# DcDc5V.net
KiCad netlist of a schematic drawn in Altium Designer
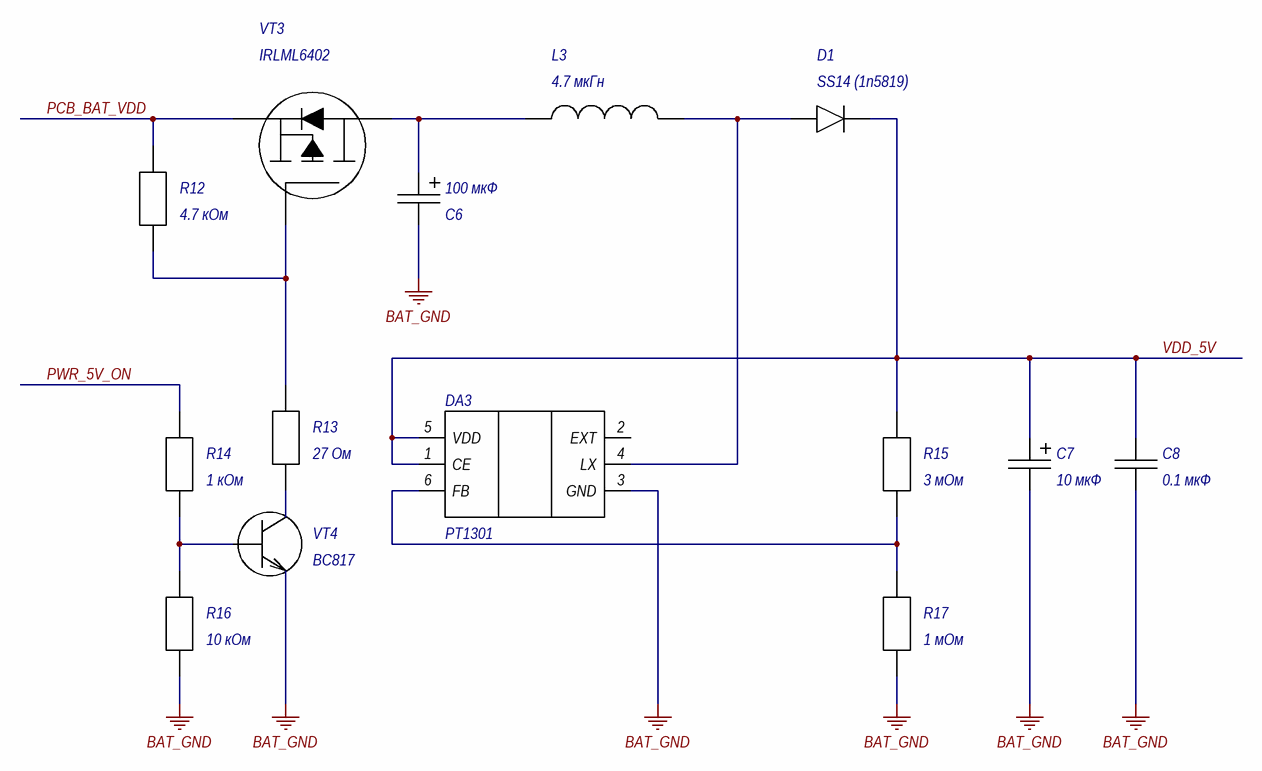
[diagram p0: DcDc5V.SchDoc]

(export (version "E")
  (design (tool "Eeschema 10.0.6"))
  (components
    (comp (ref "C6")
      (value "100 мкФ")
      (footprint "C TAN_C")
      (description "SMD Tantalium Capacitor C")
      (libsource (lib "my_lib") (part "CAP TAN_C"))
    )
    (comp (ref "C7")
      (value "10 мкФ")
      (footprint "C TAN_A")
      (description "SMD Tantalium Capacitor A")
      (libsource (lib "my_lib") (part "CAP TAN_A"))
    )
    (comp (ref "C8")
      (value "0.1 мкФ")
      (footprint "C 0805")
      (description "SMD Capacitor 0805")
      (fields
        (field (name "TOLERANCE") "/Укажите допуск в процентах/")
        (field (name "MANUFACTURER") "/Укажите компанию-производителя/")
      )
      (libsource (lib "my_lib") (part "CAP 0805"))
    )
    (comp (ref "D1")
      (value "SS14 (1n5819)")
      (footprint "SMA/DO-214AC")
      (libsource (lib "my_lib") (part "D SS14 (1n5819)"))
    )
    (comp (ref "DA3")
      (value "PT1301")
      (footprint "SOT-23-6")
      (description "DC-DC step-up (повышающий) PT1301 в корпусе SOT23-6.")
      (libsource (lib "my_lib") (part "PT1301"))
    )
    (comp (ref "L3")
      (value "4.7 мкГн")
      (footprint "CD43")
      (description "Катушка индуктивности 4.7 мкГн корпус CD43 (индуктивность 4.7 uH).")
      (libsource (lib "my_lib") (part "L 4.7 uH"))
    )
    (comp (ref "R12") (value "4.7 кОм") (footprint "RES 0402") (libsource (lib "my_lib") (part "RES 0402")))
    (comp (ref "R13") (value "27 Ом") (footprint "RES 0402") (libsource (lib "my_lib") (part "RES 0402")))
    (comp (ref "R14") (value "1 кОм") (footprint "RES 0402") (libsource (lib "my_lib") (part "RES 0402")))
    (comp (ref "R15") (value "3 мОм") (footprint "RES 0402") (libsource (lib "my_lib") (part "RES 0402")))
    (comp (ref "R16") (value "10 кОм") (footprint "RES 0402") (libsource (lib "my_lib") (part "RES 0402")))
    (comp (ref "R17") (value "1 мОм") (footprint "RES 0402") (libsource (lib "my_lib") (part "RES 0402")))
    (comp (ref "VT3") (value "IRLML6402") (footprint "SOT-23") (libsource (lib "my_lib") (part "IRLML6402")))
    (comp (ref "VT4")
      (value "BC817")
      (footprint "SOT-23")
      (description "NPN general-purpose transistor")
      (fields (field (name "MANUFACTURER") "NXP"))
      (libsource (lib "my_lib") (part "BC817"))
    )
  )
  (nets
    (net (code "1") (name "/PCB_BAT_VDD") (class "Default")
      (node (ref "R12") (pin "2") (pinfunction "2_2") (pintype "passive"))
      (node (ref "VT3") (pin "2") (pinfunction "S_2") (pintype "passive"))
    )
    (net (code "2") (name "/PWR_5V_ON") (class "Default")
      (node (ref "R14") (pin "2") (pinfunction "2_2") (pintype "passive"))
    )
    (net (code "3") (name "/VDD_5V") (class "Default")
      (node (ref "C7") (pin "1") (pinfunction "1_1") (pintype "passive"))
      (node (ref "C8") (pin "1") (pinfunction "1_1") (pintype "passive"))
      (node (ref "D1") (pin "C") (pinfunction "C_C") (pintype "passive"))
      (node (ref "DA3") (pin "1") (pinfunction "CE_1") (pintype "passive"))
      (node (ref "DA3") (pin "5") (pinfunction "VDD_5") (pintype "passive"))
      (node (ref "R15") (pin "2") (pinfunction "2_2") (pintype "passive"))
    )
    (net (code "4") (name "BAT_GND") (class "Default")
      (node (ref "C6") (pin "2") (pinfunction "2_2") (pintype "passive"))
      (node (ref "C7") (pin "2") (pinfunction "2_2") (pintype "passive"))
      (node (ref "C8") (pin "2") (pinfunction "2_2") (pintype "passive"))
      (node (ref "DA3") (pin "3") (pinfunction "GND_3") (pintype "passive"))
      (node (ref "R16") (pin "1") (pinfunction "1_1") (pintype "passive"))
      (node (ref "R17") (pin "1") (pinfunction "1_1") (pintype "passive"))
      (node (ref "VT4") (pin "2") (pinfunction "E_2") (pintype "passive"))
    )
    (net (code "5") (name "Net-(DA3-FB)") (class "Default")
      (node (ref "DA3") (pin "6") (pinfunction "FB_6") (pintype "passive"))
      (node (ref "R15") (pin "1") (pinfunction "1_1") (pintype "passive"))
      (node (ref "R17") (pin "2") (pinfunction "2_2") (pintype "passive"))
    )
    (net (code "6") (name "Net-(DA3-LX)") (class "Default")
      (node (ref "D1") (pin "A") (pinfunction "A_A") (pintype "passive"))
      (node (ref "DA3") (pin "4") (pinfunction "LX_4") (pintype "passive"))
      (node (ref "L3") (pin "2") (pinfunction "2_2") (pintype "passive"))
    )
    (net (code "7") (name "Net-(VT3-D)") (class "Default")
      (node (ref "C6") (pin "1") (pinfunction "1_1") (pintype "passive"))
      (node (ref "L3") (pin "1") (pinfunction "1_1") (pintype "passive"))
      (node (ref "VT3") (pin "3") (pinfunction "D_3") (pintype "passive"))
    )
    (net (code "8") (name "Net-(VT3-G)") (class "Default")
      (node (ref "R12") (pin "1") (pinfunction "1_1") (pintype "passive"))
      (node (ref "R13") (pin "2") (pinfunction "2_2") (pintype "passive"))
      (node (ref "VT3") (pin "1") (pinfunction "G_1") (pintype "passive"))
    )
    (net (code "9") (name "Net-(VT4-B)") (class "Default")
      (node (ref "R14") (pin "1") (pinfunction "1_1") (pintype "passive"))
      (node (ref "R16") (pin "2") (pinfunction "2_2") (pintype "passive"))
      (node (ref "VT4") (pin "1") (pinfunction "B_1") (pintype "passive"))
    )
    (net (code "10") (name "Net-(VT4-C)") (class "Default")
      (node (ref "R13") (pin "1") (pinfunction "1_1") (pintype "passive"))
      (node (ref "VT4") (pin "3") (pinfunction "C_3") (pintype "passive"))
    )
    (net (code "11") (name "unconnected-(DA3-EXT-Pad2)") (class "Default")
      (node (ref "DA3") (pin "2") (pinfunction "EXT_2") (pintype "passive"))
    )
  )
)
